# Stick.net
KiCad netlist of a schematic drawn in EAGLE
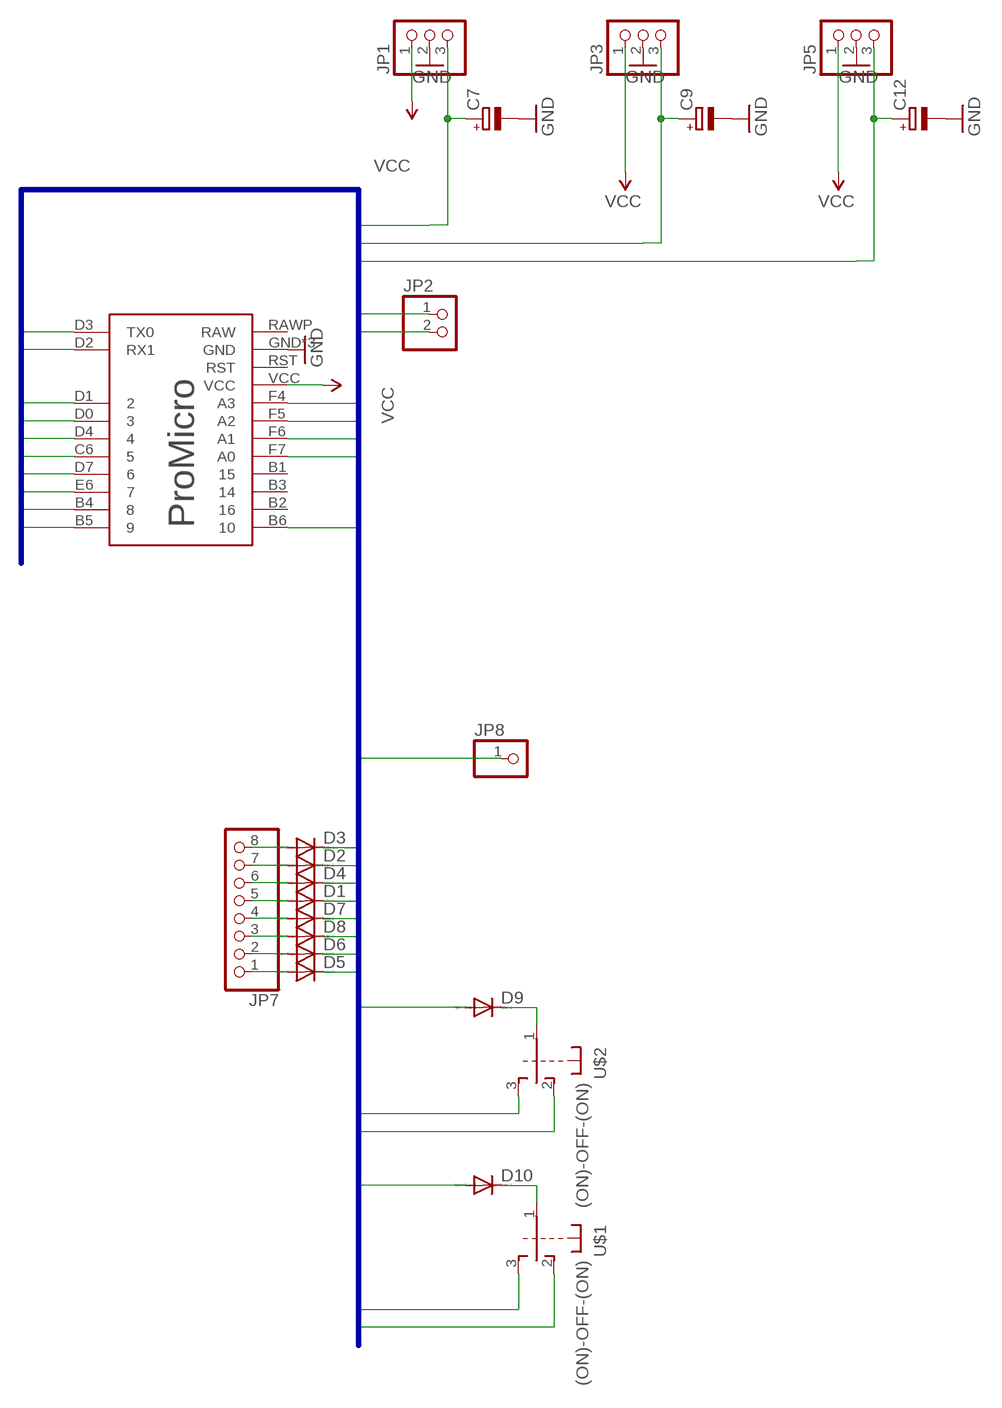
[diagram p0: schematic, sheet 1]

(export (version "E")
  (design (tool "Eeschema 10.0.6"))
  (components
    (comp (ref "C7")
      (value "CPOL-EUE2.5-5")
      (footprint "eagle-import:E2,5-5")
      (libsource (lib "eagle-import") (part "CPOL-EUE2.5-5"))
    )
    (comp (ref "C9")
      (value "CPOL-EUE2.5-5")
      (footprint "eagle-import:E2,5-5")
      (libsource (lib "eagle-import") (part "CPOL-EUE2.5-5"))
    )
    (comp (ref "C12")
      (value "CPOL-EUE2.5-5")
      (footprint "eagle-import:E2,5-5")
      (libsource (lib "eagle-import") (part "CPOL-EUE2.5-5"))
    )
    (comp (ref "D1")
      (value "DIODE-MINIMELF")
      (footprint "eagle-import:MINIMELF")
      (libsource (lib "eagle-import") (part "DIODE-MINIMELF"))
    )
    (comp (ref "D2")
      (value "DIODE-MINIMELF")
      (footprint "eagle-import:MINIMELF")
      (libsource (lib "eagle-import") (part "DIODE-MINIMELF"))
    )
    (comp (ref "D3")
      (value "DIODE-MINIMELF")
      (footprint "eagle-import:MINIMELF")
      (libsource (lib "eagle-import") (part "DIODE-MINIMELF"))
    )
    (comp (ref "D4")
      (value "DIODE-MINIMELF")
      (footprint "eagle-import:MINIMELF")
      (libsource (lib "eagle-import") (part "DIODE-MINIMELF"))
    )
    (comp (ref "D5")
      (value "DIODE-MINIMELF")
      (footprint "eagle-import:MINIMELF")
      (libsource (lib "eagle-import") (part "DIODE-MINIMELF"))
    )
    (comp (ref "D6")
      (value "DIODE-MINIMELF")
      (footprint "eagle-import:MINIMELF")
      (libsource (lib "eagle-import") (part "DIODE-MINIMELF"))
    )
    (comp (ref "D7")
      (value "DIODE-MINIMELF")
      (footprint "eagle-import:MINIMELF")
      (libsource (lib "eagle-import") (part "DIODE-MINIMELF"))
    )
    (comp (ref "D8")
      (value "DIODE-MINIMELF")
      (footprint "eagle-import:MINIMELF")
      (libsource (lib "eagle-import") (part "DIODE-MINIMELF"))
    )
    (comp (ref "D9")
      (value "DIODE-MINIMELF")
      (footprint "eagle-import:MINIMELF")
      (libsource (lib "eagle-import") (part "DIODE-MINIMELF"))
    )
    (comp (ref "D10")
      (value "DIODE-MINIMELF")
      (footprint "eagle-import:MINIMELF")
      (libsource (lib "eagle-import") (part "DIODE-MINIMELF"))
    )
    (comp (ref "JP1")
      (value "PINHD-1X3")
      (footprint "eagle-import:1X03")
      (libsource (lib "eagle-import") (part "PINHD-1X3"))
    )
    (comp (ref "JP2")
      (value "PINHD-1X2")
      (footprint "eagle-import:1X02")
      (libsource (lib "eagle-import") (part "PINHD-1X2"))
    )
    (comp (ref "JP3")
      (value "PINHD-1X3")
      (footprint "eagle-import:1X03")
      (libsource (lib "eagle-import") (part "PINHD-1X3"))
    )
    (comp (ref "JP5")
      (value "PINHD-1X3")
      (footprint "eagle-import:1X03")
      (libsource (lib "eagle-import") (part "PINHD-1X3"))
    )
    (comp (ref "JP7")
      (value "PINHD-1X8")
      (footprint "eagle-import:1X08")
      (libsource (lib "eagle-import") (part "PINHD-1X8"))
    )
    (comp (ref "JP8")
      (value "PINHD-1X1")
      (footprint "eagle-import:1X01")
      (libsource (lib "eagle-import") (part "PINHD-1X1"))
    )
    (comp (ref "U$1")
      (value "(ON)-OFF-(ON)")
      (footprint "eagle-import:SWITCH-(ON)-OFF-(ON)")
      (libsource (lib "eagle-import") (part "(ON)-OFF-(ON)"))
    )
    (comp (ref "U$2")
      (value "(ON)-OFF-(ON)")
      (footprint "eagle-import:SWITCH-(ON)-OFF-(ON)")
      (libsource (lib "eagle-import") (part "(ON)-OFF-(ON)"))
    )
    (comp (ref "U$3")
      (value "SPARKFUN")
      (footprint "eagle-import:PRO-MICRO")
      (libsource (lib "eagle-import") (part "SPARKFUN"))
    )
  )
  (nets
    (net (code "1") (name "/A1") (class "Default")
      (node (ref "C7") (pin "+") (pinfunction "+_+") (pintype "passive"))
      (node (ref "JP1") (pin "3") (pinfunction "3_3") (pintype "passive"))
      (node (ref "U$3") (pin "F4") (pinfunction "A3_F4") (pintype "bidirectional"))
    )
    (net (code "2") (name "/A2") (class "Default")
      (node (ref "C9") (pin "+") (pinfunction "+_+") (pintype "passive"))
      (node (ref "JP3") (pin "3") (pinfunction "3_3") (pintype "passive"))
      (node (ref "U$3") (pin "F5") (pinfunction "A2_F5") (pintype "bidirectional"))
    )
    (net (code "3") (name "/A3") (class "Default")
      (node (ref "C12") (pin "+") (pinfunction "+_+") (pintype "passive"))
      (node (ref "JP5") (pin "3") (pinfunction "3_3") (pintype "passive"))
      (node (ref "U$3") (pin "F6") (pinfunction "A1_F6") (pintype "bidirectional"))
    )
    (net (code "4") (name "/A4") (class "Default")
      (node (ref "JP2") (pin "1") (pinfunction "1_1") (pintype "passive"))
      (node (ref "U$3") (pin "F7") (pinfunction "A0_F7") (pintype "bidirectional"))
    )
    (net (code "5") (name "/A5") (class "Default")
      (node (ref "JP2") (pin "2") (pinfunction "2_2") (pintype "passive"))
      (node (ref "U$3") (pin "B6") (pinfunction "10_B6") (pintype "bidirectional"))
    )
    (net (code "6") (name "/C1") (class "Default")
      (node (ref "JP8") (pin "1") (pinfunction "1_1") (pintype "passive"))
      (node (ref "U$3") (pin "D2") (pinfunction "RX1_D2") (pintype "bidirectional"))
    )
    (net (code "7") (name "/C2") (class "Default")
      (node (ref "D10") (pin "A") (pinfunction "A_A") (pintype "passive"))
      (node (ref "D9") (pin "A") (pinfunction "A_A") (pintype "passive"))
      (node (ref "U$3") (pin "D3") (pinfunction "TX0_D3") (pintype "bidirectional"))
    )
    (net (code "8") (name "/R1") (class "Default")
      (node (ref "D5") (pin "C") (pinfunction "C_C") (pintype "passive"))
      (node (ref "U$3") (pin "D1") (pinfunction "2_D1") (pintype "bidirectional"))
    )
    (net (code "9") (name "/R2") (class "Default")
      (node (ref "D6") (pin "C") (pinfunction "C_C") (pintype "passive"))
      (node (ref "U$2") (pin "2") (pinfunction "2_2") (pintype "passive"))
      (node (ref "U$3") (pin "D0") (pinfunction "3_D0") (pintype "bidirectional"))
    )
    (net (code "10") (name "/R3") (class "Default")
      (node (ref "D8") (pin "C") (pinfunction "C_C") (pintype "passive"))
      (node (ref "U$2") (pin "3") (pinfunction "3_3") (pintype "passive"))
      (node (ref "U$3") (pin "D4") (pinfunction "4_D4") (pintype "bidirectional"))
    )
    (net (code "11") (name "/R4") (class "Default")
      (node (ref "D7") (pin "C") (pinfunction "C_C") (pintype "passive"))
      (node (ref "U$1") (pin "2") (pinfunction "2_2") (pintype "passive"))
      (node (ref "U$3") (pin "C6") (pinfunction "5_C6") (pintype "bidirectional"))
    )
    (net (code "12") (name "/R5") (class "Default")
      (node (ref "D1") (pin "C") (pinfunction "C_C") (pintype "passive"))
      (node (ref "U$1") (pin "3") (pinfunction "3_3") (pintype "passive"))
      (node (ref "U$3") (pin "D7") (pinfunction "6_D7") (pintype "bidirectional"))
    )
    (net (code "13") (name "/R6") (class "Default")
      (node (ref "D4") (pin "C") (pinfunction "C_C") (pintype "passive"))
      (node (ref "U$3") (pin "E6") (pinfunction "7_E6") (pintype "bidirectional"))
    )
    (net (code "14") (name "/R7") (class "Default")
      (node (ref "D2") (pin "C") (pinfunction "C_C") (pintype "passive"))
      (node (ref "U$3") (pin "B4") (pinfunction "8_B4") (pintype "bidirectional"))
    )
    (net (code "15") (name "/R8") (class "Default")
      (node (ref "D3") (pin "C") (pinfunction "C_C") (pintype "passive"))
      (node (ref "U$3") (pin "B5") (pinfunction "9_B5") (pintype "bidirectional"))
    )
    (net (code "16") (name "GND") (class "Default")
      (node (ref "C12") (pin "-") (pinfunction "-_-") (pintype "passive"))
      (node (ref "C7") (pin "-") (pinfunction "-_-") (pintype "passive"))
      (node (ref "C9") (pin "-") (pinfunction "-_-") (pintype "passive"))
      (node (ref "JP1") (pin "2") (pinfunction "2_2") (pintype "passive"))
      (node (ref "JP3") (pin "2") (pinfunction "2_2") (pintype "passive"))
      (node (ref "JP5") (pin "2") (pinfunction "2_2") (pintype "passive"))
      (node (ref "U$3") (pin "GND") (pinfunction "GND_GND") (pintype "bidirectional"))
      (node (ref "U$3") (pin "GND3") (pinfunction "GND_GND3") (pintype "bidirectional"))
      (node (ref "U$3") (pin "GND4") (pinfunction "GND_GND4") (pintype "bidirectional"))
    )
    (net (code "17") (name "Net-(D1-PadA)") (class "Default")
      (node (ref "D1") (pin "A") (pinfunction "A_A") (pintype "passive"))
      (node (ref "JP7") (pin "5") (pinfunction "5_5") (pintype "passive"))
    )
    (net (code "18") (name "Net-(D2-PadA)") (class "Default")
      (node (ref "D2") (pin "A") (pinfunction "A_A") (pintype "passive"))
      (node (ref "JP7") (pin "7") (pinfunction "7_7") (pintype "passive"))
    )
    (net (code "19") (name "Net-(D3-PadA)") (class "Default")
      (node (ref "D3") (pin "A") (pinfunction "A_A") (pintype "passive"))
      (node (ref "JP7") (pin "8") (pinfunction "8_8") (pintype "passive"))
    )
    (net (code "20") (name "Net-(D4-PadA)") (class "Default")
      (node (ref "D4") (pin "A") (pinfunction "A_A") (pintype "passive"))
      (node (ref "JP7") (pin "6") (pinfunction "6_6") (pintype "passive"))
    )
    (net (code "21") (name "Net-(D5-PadA)") (class "Default")
      (node (ref "D5") (pin "A") (pinfunction "A_A") (pintype "passive"))
      (node (ref "JP7") (pin "1") (pinfunction "1_1") (pintype "passive"))
    )
    (net (code "22") (name "Net-(D6-PadA)") (class "Default")
      (node (ref "D6") (pin "A") (pinfunction "A_A") (pintype "passive"))
      (node (ref "JP7") (pin "2") (pinfunction "2_2") (pintype "passive"))
    )
    (net (code "23") (name "Net-(D7-PadA)") (class "Default")
      (node (ref "D7") (pin "A") (pinfunction "A_A") (pintype "passive"))
      (node (ref "JP7") (pin "4") (pinfunction "4_4") (pintype "passive"))
    )
    (net (code "24") (name "Net-(D8-PadA)") (class "Default")
      (node (ref "D8") (pin "A") (pinfunction "A_A") (pintype "passive"))
      (node (ref "JP7") (pin "3") (pinfunction "3_3") (pintype "passive"))
    )
    (net (code "25") (name "Net-(D9-PadC)") (class "Default")
      (node (ref "D9") (pin "C") (pinfunction "C_C") (pintype "passive"))
      (node (ref "U$2") (pin "1") (pinfunction "1_1") (pintype "passive"))
    )
    (net (code "26") (name "Net-(D10-PadC)") (class "Default")
      (node (ref "D10") (pin "C") (pinfunction "C_C") (pintype "passive"))
      (node (ref "U$1") (pin "1") (pinfunction "1_1") (pintype "passive"))
    )
    (net (code "27") (name "VCC") (class "Default")
      (node (ref "JP1") (pin "1") (pinfunction "1_1") (pintype "passive"))
      (node (ref "JP3") (pin "1") (pinfunction "1_1") (pintype "passive"))
      (node (ref "JP5") (pin "1") (pinfunction "1_1") (pintype "passive"))
      (node (ref "U$3") (pin "VCC") (pinfunction "VCC_VCC") (pintype "bidirectional"))
    )
    (net (code "28") (name "unconnected-(U$3-14-PadB3)") (class "Default")
      (node (ref "U$3") (pin "B3") (pinfunction "14_B3") (pintype "bidirectional"))
    )
    (net (code "29") (name "unconnected-(U$3-15-PadB1)") (class "Default")
      (node (ref "U$3") (pin "B1") (pinfunction "15_B1") (pintype "bidirectional"))
    )
    (net (code "30") (name "unconnected-(U$3-16-PadB2)") (class "Default")
      (node (ref "U$3") (pin "B2") (pinfunction "16_B2") (pintype "bidirectional"))
    )
    (net (code "31") (name "unconnected-(U$3-PadRST)") (class "Default")
      (node (ref "U$3") (pin "RST") (pinfunction "RST_RST") (pintype "bidirectional"))
    )
    (net (code "32") (name "unconnected-(U$3-RAW-PadRAWP)") (class "Default")
      (node (ref "U$3") (pin "RAWP") (pinfunction "RAW_RAWP") (pintype "bidirectional"))
    )
  )
)
